# 7805.net
KiCad netlist of a schematic drawn in EAGLE
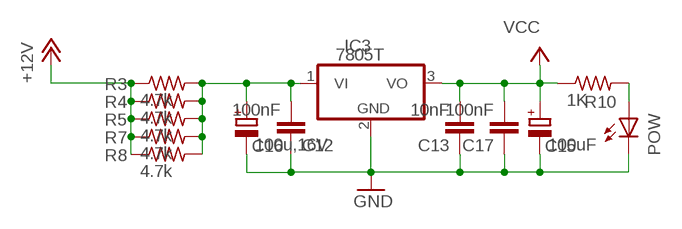
[diagram p0: schematic, sheet 1]

(export (version "E")
  (design (tool "Eeschema 10.0.6"))
  (components
    (comp (ref "C12")
      (value "100nF")
      (footprint "eagle-import:C050-024X044")
      (libsource (lib "eagle-import") (part "C-EU050-024X044"))
    )
    (comp (ref "C13")
      (value "10nF")
      (footprint "eagle-import:C050-024X044")
      (libsource (lib "eagle-import") (part "C-EU050-024X044"))
    )
    (comp (ref "C15")
      (value "100uF")
      (footprint "eagle-import:TT2D6")
      (libsource (lib "eagle-import") (part "CPOL-EUTT2D6"))
    )
    (comp (ref "C16")
      (value "100u,16V")
      (footprint "eagle-import:TT2D6")
      (libsource (lib "eagle-import") (part "CPOL-EUTT2D6"))
    )
    (comp (ref "C17")
      (value "100nF")
      (footprint "eagle-import:C050-024X044")
      (libsource (lib "eagle-import") (part "C-EU050-024X044"))
    )
    (comp (ref "IC3")
      (value "7805T")
      (footprint "eagle-import:TO220H")
      (libsource (lib "eagle-import") (part "78T05"))
    )
    (comp (ref "POW")
      (value "LED3MM")
      (footprint "eagle-import:LED3MM")
      (libsource (lib "eagle-import") (part "LED3MM"))
    )
    (comp (ref "R3")
      (value "4.7k")
      (footprint "eagle-import:0204_7")
      (libsource (lib "eagle-import") (part "R-US_0204/7"))
    )
    (comp (ref "R4")
      (value "4.7k")
      (footprint "eagle-import:0204_7")
      (libsource (lib "eagle-import") (part "R-US_0204/7"))
    )
    (comp (ref "R5")
      (value "4.7k")
      (footprint "eagle-import:0204_7")
      (libsource (lib "eagle-import") (part "R-US_0204/7"))
    )
    (comp (ref "R7")
      (value "4.7k")
      (footprint "eagle-import:0204_7")
      (libsource (lib "eagle-import") (part "R-US_0204/7"))
    )
    (comp (ref "R8")
      (value "4.7k")
      (footprint "eagle-import:0204_7")
      (libsource (lib "eagle-import") (part "R-US_0204/7"))
    )
    (comp (ref "R10")
      (value "1K")
      (footprint "eagle-import:0204_7")
      (libsource (lib "eagle-import") (part "R-US_0204/7"))
    )
  )
  (nets
    (net (code "1") (name "+12V") (class "Default")
      (node (ref "R3") (pin "1") (pinfunction "1_1") (pintype "passive"))
      (node (ref "R4") (pin "1") (pinfunction "1_1") (pintype "passive"))
      (node (ref "R5") (pin "1") (pinfunction "1_1") (pintype "passive"))
      (node (ref "R7") (pin "1") (pinfunction "1_1") (pintype "passive"))
      (node (ref "R8") (pin "1") (pinfunction "1_1") (pintype "passive"))
    )
    (net (code "2") (name "GND") (class "Default")
      (node (ref "C12") (pin "1") (pinfunction "1_1") (pintype "passive"))
      (node (ref "C13") (pin "1") (pinfunction "1_1") (pintype "passive"))
      (node (ref "C15") (pin "-") (pinfunction "-_-") (pintype "passive"))
      (node (ref "C16") (pin "-") (pinfunction "-_-") (pintype "passive"))
      (node (ref "C17") (pin "1") (pinfunction "1_1") (pintype "passive"))
      (node (ref "IC3") (pin "2") (pinfunction "GND_2") (pintype "passive"))
      (node (ref "POW") (pin "K") (pinfunction "C_K") (pintype "passive"))
    )
    (net (code "3") (name "Net-(IC3-VI)") (class "Default")
      (node (ref "C12") (pin "2") (pinfunction "2_2") (pintype "passive"))
      (node (ref "C16") (pin "+") (pinfunction "+_+") (pintype "passive"))
      (node (ref "IC3") (pin "1") (pinfunction "VI_1") (pintype "input"))
      (node (ref "R3") (pin "2") (pinfunction "2_2") (pintype "passive"))
      (node (ref "R4") (pin "2") (pinfunction "2_2") (pintype "passive"))
      (node (ref "R5") (pin "2") (pinfunction "2_2") (pintype "passive"))
      (node (ref "R7") (pin "2") (pinfunction "2_2") (pintype "passive"))
      (node (ref "R8") (pin "2") (pinfunction "2_2") (pintype "passive"))
    )
    (net (code "4") (name "Net-(POW-PadA)") (class "Default")
      (node (ref "POW") (pin "A") (pinfunction "A_A") (pintype "passive"))
      (node (ref "R10") (pin "2") (pinfunction "2_2") (pintype "passive"))
    )
    (net (code "5") (name "VCC") (class "Default")
      (node (ref "C13") (pin "2") (pinfunction "2_2") (pintype "passive"))
      (node (ref "C15") (pin "+") (pinfunction "+_+") (pintype "passive"))
      (node (ref "C17") (pin "2") (pinfunction "2_2") (pintype "passive"))
      (node (ref "IC3") (pin "3") (pinfunction "VO_3") (pintype "passive"))
      (node (ref "R10") (pin "1") (pinfunction "1_1") (pintype "passive"))
    )
  )
)
